# BtnCore.net
KiCad netlist of a schematic drawn in Altium Designer
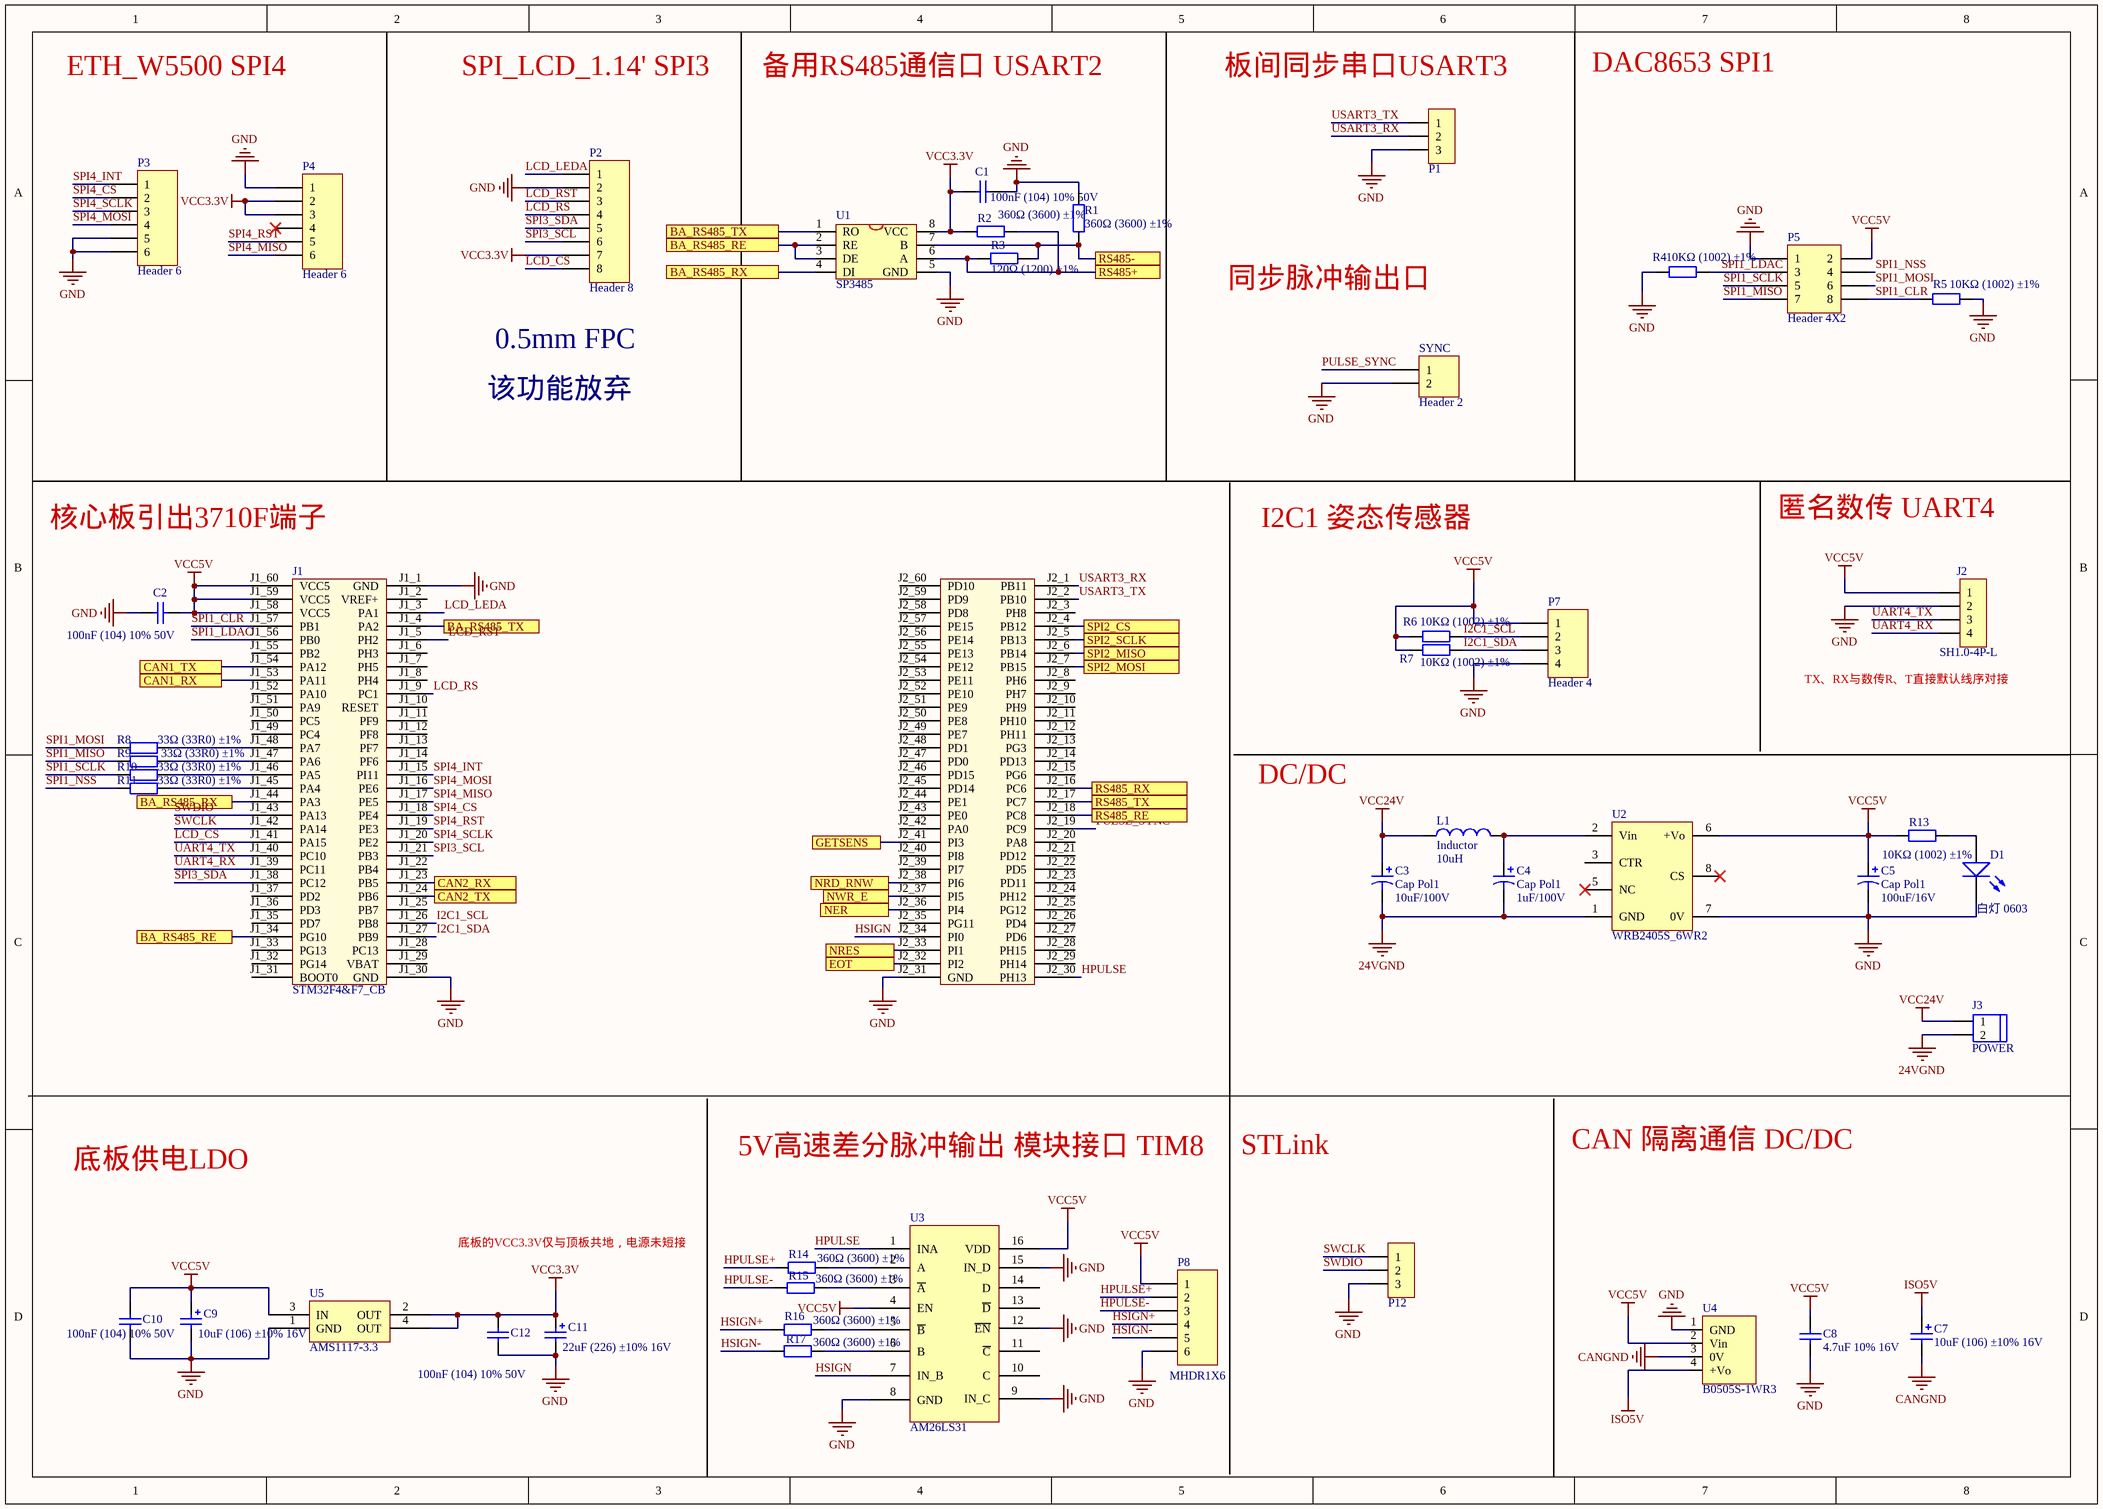
[diagram p0: BtnCore.SchDoc]

(export (version "E")
  (design (tool "Eeschema 10.0.6"))
  (components
    (comp (ref "C1")
      (value "100nF (104) 10% 50V")
      (footprint "0402_C")
      (description "贴片电容")
      (libsource (lib "Cap") (part "0603 100nF (104) 10% 50V"))
    )
    (comp (ref "C2")
      (value "100nF (104) 10% 50V")
      (footprint "0402_C")
      (description "贴片电容")
      (libsource (lib "Cap") (part "0603 100nF (104) 10% 50V"))
    )
    (comp (ref "C3")
      (value "Cap Pol1")
      (footprint "CAP-E8mm")
      (description "Polarized Capacitor (Radial)")
      (fields (field (name "ALTIUM_VALUE") "10uF/100V") (field (name "PUBLISHER") "Altium Limited"))
      (libsource (lib "Miscellaneous Devices") (part "Cap Pol1"))
    )
    (comp (ref "C4")
      (value "Cap Pol1")
      (footprint "CAP-E5mm")
      (description "Polarized Capacitor (Radial)")
      (fields (field (name "ALTIUM_VALUE") "1uF/100V") (field (name "PUBLISHER") "Altium Limited"))
      (libsource (lib "Miscellaneous Devices") (part "Cap Pol1"))
    )
    (comp (ref "C5")
      (value "Cap Pol1")
      (footprint "CAP-E8mm")
      (description "Polarized Capacitor (Radial)")
      (fields (field (name "ALTIUM_VALUE") "100uF/16V") (field (name "PUBLISHER") "Altium Limited"))
      (libsource (lib "Miscellaneous Devices") (part "Cap Pol1"))
    )
    (comp (ref "C7")
      (value "10uF (106) ±10% 16V")
      (footprint "CASE-A_3216")
      (description "钽电容")
      (libsource (lib "Miscellaneous Devices LC") (part "3216 10uF (106) 10% 16V"))
    )
    (comp (ref "C8")
      (value "4.7uF 10% 16V")
      (footprint "0603_C")
      (description "贴片电容")
      (libsource (lib "Cap") (part "0603 100nF (104) 10% 50V"))
    )
    (comp (ref "C9")
      (value "10uF (106) ±10% 16V")
      (footprint "CASE-A_3216")
      (description "钽电容")
      (libsource (lib "Cap") (part "3216 10uF (106) 10% 16V"))
    )
    (comp (ref "C10")
      (value "100nF (104) 10% 50V")
      (footprint "0402_C")
      (description "贴片电容")
      (libsource (lib "Cap") (part "0603 100nF (104) 10% 50V"))
    )
    (comp (ref "C11")
      (value "22uF (226) ±10% 16V")
      (footprint "CASE-B_3528")
      (description "钽电容")
      (libsource (lib "Cap") (part "3216 10uF (106) 10% 16V"))
    )
    (comp (ref "C12")
      (value "100nF (104) 10% 50V")
      (footprint "0402_C")
      (description "贴片电容")
      (libsource (lib "Cap") (part "0603 100nF (104) 10% 50V"))
    )
    (comp (ref "D1")
      (value "白灯 0603")
      (footprint "0603_LED_S1")
      (description "发光二极管")
      (libsource (lib "LED") (part "0603 白灯"))
    )
    (comp (ref "J1")
      (value "STM32F4&F7_CB")
      (footprint "STM32F4&F7_CB")
      (description "F429/746 Core Board")
      (libsource (lib "STM32F429_F746") (part "STM32F4&F7_CB"))
    )
    (comp (ref "J2")
      (value "SH1.0-4P-L")
      (footprint "SH1.0-4P-L")
      (description "4P接插件")
      (libsource (lib "4.14接插件-脚距1.0") (part "Header 4"))
    )
    (comp (ref "J3")
      (value "POWER")
      (footprint "HEAD2L-0.8")
      (libsource (lib "STM32F429_F746") (part "HEAD2"))
    )
    (comp (ref "L1")
      (value "Inductor")
      (footprint "0603_L")
      (fields (field (name "ALTIUM_VALUE") "10uH") (field (name "PUBLISHER") "Altium Limited"))
      (libsource (lib "Miscellaneous Devices") (part "Inductor"))
    )
    (comp (ref "P1")
      (value "SH1.0-3P")
      (footprint "SH1.0-3P-L")
      (description "3P接插件")
      (libsource (lib "4.14接插件-脚距1.0") (part "Header 3"))
    )
    (comp (ref "P2")
      (value "Header 8")
      (footprint "FPC0.5 2H-WS-8P")
      (description "Header, 8-Pin")
      (fields (field (name "PUBLISHER") "Altium Limited"))
      (libsource (lib "Miscellaneous Connectors") (part "Header 8"))
    )
    (comp (ref "P3")
      (value "Header 6")
      (footprint "HDR1X6")
      (description "Header, 6-Pin")
      (fields (field (name "PUBLISHER") "Altium Limited"))
      (libsource (lib "Miscellaneous Connectors") (part "Header 6"))
    )
    (comp (ref "P4")
      (value "Header 6")
      (footprint "HDR1X6")
      (description "Header, 6-Pin")
      (fields (field (name "PUBLISHER") "Altium Limited"))
      (libsource (lib "Miscellaneous Connectors") (part "Header 6"))
    )
    (comp (ref "P5")
      (value "Header 4X2")
      (footprint "HDR2X4")
      (description "Header, 4-Pin, Dual row")
      (fields (field (name "PUBLISHER") "Altium Limited"))
      (libsource (lib "Miscellaneous Connectors") (part "Header 4X2"))
    )
    (comp (ref "P7")
      (value "Header 4")
      (footprint "SH1.0-4P-L")
      (description "Header, 4-Pin")
      (fields (field (name "PUBLISHER") "Altium Limited"))
      (libsource (lib "Miscellaneous Connectors") (part "Header 4"))
    )
    (comp (ref "P8")
      (value "MHDR1X6")
      (footprint "SH1.0-6P-L")
      (description "Header, 6-Pin")
      (fields (field (name "PUBLISHER") "Altium Limited"))
      (libsource (lib "Miscellaneous Connectors") (part "MHDR1X6"))
    )
    (comp (ref "P12")
      (value "SH1.0-3P")
      (footprint "SH1.0-3P-L")
      (description "3P接插件")
      (libsource (lib "4.14接插件-脚距1.0") (part "Header 3"))
    )
    (comp (ref "R1")
      (value "360Ω (3600) ±1%")
      (footprint "0402_R")
      (description "贴片电阻")
      (libsource (lib "RES") (part "0603 360Ω (3600) 1%"))
    )
    (comp (ref "R2")
      (value "360Ω (3600) ±1%")
      (footprint "0402_R")
      (description "贴片电阻")
      (libsource (lib "") (part "0603 360Ω (3600) 1%_2"))
    )
    (comp (ref "R3")
      (value "120Ω (1200) ±1%")
      (footprint "0402_R")
      (description "贴片电阻")
      (libsource (lib "RES") (part "0603 120Ω (1200) 1%"))
    )
    (comp (ref "R4")
      (value "10KΩ (1002) ±1%")
      (footprint "0402_R")
      (description "贴片电阻")
      (libsource (lib "RES") (part "0805 100KΩ (1003) 1%"))
    )
    (comp (ref "R5")
      (value "10KΩ (1002) ±1%")
      (footprint "0402_R")
      (description "贴片电阻")
      (libsource (lib "RES") (part "0805 100KΩ (1003) 1%"))
    )
    (comp (ref "R6")
      (value "10KΩ (1002) ±1%")
      (footprint "0402_R")
      (description "贴片电阻")
      (libsource (lib "") (part "0805 100KΩ (1003) 1%_1"))
    )
    (comp (ref "R7")
      (value "10KΩ (1002) ±1%")
      (footprint "0402_R")
      (description "贴片电阻")
      (libsource (lib "") (part "0805 100KΩ (1003) 1%_1"))
    )
    (comp (ref "R8")
      (value "33Ω (33R0) ±1%")
      (footprint "0402_R")
      (description "贴片电阻")
      (libsource (lib "Miscellaneous Devices LC") (part "0603 33Ω (33R0) 1%"))
    )
    (comp (ref "R9")
      (value "33Ω (33R0) ±1%")
      (footprint "0402_R")
      (description "贴片电阻")
      (libsource (lib "Miscellaneous Devices LC") (part "0603 33Ω (33R0) 1%"))
    )
    (comp (ref "R10")
      (value "33Ω (33R0) ±1%")
      (footprint "0402_R")
      (description "贴片电阻")
      (libsource (lib "Miscellaneous Devices LC") (part "0603 33Ω (33R0) 1%"))
    )
    (comp (ref "R11")
      (value "33Ω (33R0) ±1%")
      (footprint "0402_R")
      (description "贴片电阻")
      (libsource (lib "Miscellaneous Devices LC") (part "0603 33Ω (33R0) 1%"))
    )
    (comp (ref "R13")
      (value "10KΩ (1002) ±1%")
      (footprint "0402_R")
      (description "贴片电阻")
      (libsource (lib "") (part "0805 100KΩ (1003) 1%_1"))
    )
    (comp (ref "R14")
      (value "360Ω (3600) ±1%")
      (footprint "0402_R")
      (description "贴片电阻")
      (libsource (lib "") (part "0603 360Ω (3600) 1%_1"))
    )
    (comp (ref "R15")
      (value "360Ω (3600) ±1%")
      (footprint "0402_R")
      (description "贴片电阻")
      (libsource (lib "") (part "0603 360Ω (3600) 1%_1"))
    )
    (comp (ref "R16")
      (value "360Ω (3600) ±1%")
      (footprint "0402_R")
      (description "贴片电阻")
      (libsource (lib "") (part "0603 360Ω (3600) 1%_1"))
    )
    (comp (ref "R17")
      (value "360Ω (3600) ±1%")
      (footprint "0402_R")
      (description "贴片电阻")
      (libsource (lib "") (part "0603 360Ω (3600) 1%_1"))
    )
    (comp (ref "SYNC")
      (value "Header 2")
      (footprint "HDR1X2")
      (description "Header, 2-Pin")
      (fields (field (name "PUBLISHER") "Altium Limited"))
      (libsource (lib "Miscellaneous Connectors") (part "Header 2"))
    )
    (comp (ref "U1") (value "SP3485") (footprint "SOP-8") (libsource (lib "STM32F429_F746") (part "MAX3485")))
    (comp (ref "U2")
      (value "WRB2405S_6WR2")
      (footprint "DCDC_SUCCEED-WRA_S/WRB-1/2/3W")
      (description "电源模块")
      (libsource (lib "Library") (part "DCDC-WRB"))
    )
    (comp (ref "U3")
      (value "AM26LS31")
      (footprint "SO-16_N")
      (description "AM32LS31 单端转差分芯片")
      (libsource (lib "CAS") (part "AM26LS31"))
    )
    (comp (ref "U4")
      (value "B0505S-1WR3")
      (footprint "B_S-1WR3")
      (libsource (lib "B_S-1WR3") (part "B_S-1WR3"))
    )
    (comp (ref "U5")
      (value "AMS1117-3.3")
      (footprint "SOT223_M")
      (description "3.3V稳压芯片")
      (libsource (lib "Library") (part "AMS1117"))
    )
  )
  (nets
    (net (code "1") (name "/BA_RS485_RE") (class "Default")
      (node (ref "J1") (pin "J1_34") (pinfunction "PG10_J1_34") (pintype "passive"))
      (node (ref "U1") (pin "2") (pinfunction "RE_2") (pintype "passive"))
      (node (ref "U1") (pin "3") (pinfunction "DE_3") (pintype "passive"))
    )
    (net (code "2") (name "/BA_RS485_RX") (class "Default")
      (node (ref "J1") (pin "J1_44") (pinfunction "PA3_J1_44") (pintype "passive"))
      (node (ref "U1") (pin "4") (pinfunction "DI_4") (pintype "passive"))
    )
    (net (code "3") (name "/BA_RS485_TX") (class "Default")
      (node (ref "J1") (pin "J1_4") (pinfunction "PA2_J1_4") (pintype "passive"))
      (node (ref "U1") (pin "1") (pinfunction "RO_1") (pintype "passive"))
    )
    (net (code "4") (name "/CAN1_RX") (class "Default")
      (node (ref "J1") (pin "J1_53") (pinfunction "PA11_J1_53") (pintype "passive"))
    )
    (net (code "5") (name "/CAN1_TX") (class "Default")
      (node (ref "J1") (pin "J1_54") (pinfunction "PA12_J1_54") (pintype "passive"))
    )
    (net (code "6") (name "/CAN2_RX") (class "Default")
      (node (ref "J1") (pin "J1_23") (pinfunction "PB5_J1_23") (pintype "passive"))
    )
    (net (code "7") (name "/CAN2_TX") (class "Default")
      (node (ref "J1") (pin "J1_24") (pinfunction "PB6_J1_24") (pintype "passive"))
    )
    (net (code "8") (name "/EOT") (class "Default")
      (node (ref "J1") (pin "J2_32") (pinfunction "PI2_J2_32") (pintype "passive"))
    )
    (net (code "9") (name "/GETSENS") (class "Default")
      (node (ref "J1") (pin "J2_41") (pinfunction "PI3_J2_41") (pintype "passive"))
    )
    (net (code "10") (name "/HPULSE") (class "Default")
      (node (ref "J1") (pin "J2_30") (pinfunction "PH13_J2_30") (pintype "passive"))
      (node (ref "U3") (pin "1") (pinfunction "INA_1") (pintype "passive"))
    )
    (net (code "11") (name "/HPULSE+") (class "Default")
      (node (ref "P8") (pin "2") (pinfunction "2_2") (pintype "passive"))
      (node (ref "R14") (pin "2") (pinfunction "2_2") (pintype "passive"))
    )
    (net (code "12") (name "/HPULSE-") (class "Default")
      (node (ref "P8") (pin "3") (pinfunction "3_3") (pintype "passive"))
      (node (ref "R15") (pin "2") (pinfunction "2_2") (pintype "passive"))
    )
    (net (code "13") (name "/HSIGN") (class "Default")
      (node (ref "J1") (pin "J2_34") (pinfunction "PI0_J2_34") (pintype "passive"))
      (node (ref "U3") (pin "7") (pinfunction "IN_B_7") (pintype "passive"))
    )
    (net (code "14") (name "/HSIGN+") (class "Default")
      (node (ref "P8") (pin "4") (pinfunction "4_4") (pintype "passive"))
      (node (ref "R16") (pin "2") (pinfunction "2_2") (pintype "passive"))
    )
    (net (code "15") (name "/HSIGN-") (class "Default")
      (node (ref "P8") (pin "5") (pinfunction "5_5") (pintype "passive"))
      (node (ref "R17") (pin "2") (pinfunction "2_2") (pintype "passive"))
    )
    (net (code "16") (name "/I2C1_SCL") (class "Default")
      (node (ref "J1") (pin "J1_26") (pinfunction "PB8_J1_26") (pintype "passive"))
      (node (ref "P7") (pin "2") (pinfunction "2_2") (pintype "passive"))
      (node (ref "R6") (pin "2") (pinfunction "2_2") (pintype "passive"))
    )
    (net (code "17") (name "/I2C1_SDA") (class "Default")
      (node (ref "J1") (pin "J1_27") (pinfunction "PB9_J1_27") (pintype "passive"))
      (node (ref "P7") (pin "3") (pinfunction "3_3") (pintype "passive"))
      (node (ref "R7") (pin "2") (pinfunction "2_2") (pintype "passive"))
    )
    (net (code "18") (name "/LCD_CS") (class "Default")
      (node (ref "J1") (pin "J1_41") (pinfunction "PA15_J1_41") (pintype "passive"))
      (node (ref "P2") (pin "8") (pinfunction "8_8") (pintype "passive"))
    )
    (net (code "19") (name "/LCD_LEDA") (class "Default")
      (node (ref "J1") (pin "J1_3") (pinfunction "PA1_J1_3") (pintype "passive"))
      (node (ref "P2") (pin "1") (pinfunction "1_1") (pintype "passive"))
    )
    (net (code "20") (name "/LCD_RS") (class "Default")
      (node (ref "J1") (pin "J1_9") (pinfunction "PC1_J1_9") (pintype "passive"))
      (node (ref "P2") (pin "4") (pinfunction "4_4") (pintype "passive"))
    )
    (net (code "21") (name "/LCD_RST") (class "Default")
      (node (ref "J1") (pin "J1_5") (pinfunction "PH2_J1_5") (pintype "passive"))
      (node (ref "P2") (pin "3") (pinfunction "3_3") (pintype "passive"))
    )
    (net (code "22") (name "/NER") (class "Default")
      (node (ref "J1") (pin "J2_36") (pinfunction "PI4_J2_36") (pintype "passive"))
    )
    (net (code "23") (name "/NRD_RNW") (class "Default")
      (node (ref "J1") (pin "J2_38") (pinfunction "PI6_J2_38") (pintype "passive"))
    )
    (net (code "24") (name "/NRES") (class "Default")
      (node (ref "J1") (pin "J2_33") (pinfunction "PI1_J2_33") (pintype "passive"))
    )
    (net (code "25") (name "/NWR_E") (class "Default")
      (node (ref "J1") (pin "J2_37") (pinfunction "PI5_J2_37") (pintype "passive"))
    )
    (net (code "26") (name "/PULSE_SYNC") (class "Default")
      (node (ref "J1") (pin "J2_19") (pinfunction "PC9_J2_19") (pintype "passive"))
      (node (ref "SYNC") (pin "1") (pinfunction "1_1") (pintype "passive"))
    )
    (net (code "27") (name "/RS485+") (class "Default")
      (node (ref "R2") (pin "2") (pinfunction "2_2") (pintype "passive"))
      (node (ref "R3") (pin "2") (pinfunction "2_2") (pintype "passive"))
      (node (ref "U1") (pin "6") (pinfunction "A_6") (pintype "passive"))
    )
    (net (code "28") (name "/RS485-") (class "Default")
      (node (ref "R1") (pin "1") (pinfunction "1_1") (pintype "passive"))
      (node (ref "R3") (pin "1") (pinfunction "1_1") (pintype "passive"))
      (node (ref "U1") (pin "7") (pinfunction "B_7") (pintype "passive"))
    )
    (net (code "29") (name "/RS485_RE") (class "Default")
      (node (ref "J1") (pin "J2_18") (pinfunction "PC8_J2_18") (pintype "passive"))
    )
    (net (code "30") (name "/RS485_RX") (class "Default")
      (node (ref "J1") (pin "J2_16") (pinfunction "PC6_J2_16") (pintype "passive"))
    )
    (net (code "31") (name "/RS485_TX") (class "Default")
      (node (ref "J1") (pin "J2_17") (pinfunction "PC7_J2_17") (pintype "passive"))
    )
    (net (code "32") (name "/SPI1_CLR") (class "Default")
      (node (ref "J1") (pin "J1_57") (pinfunction "PB1_J1_57") (pintype "passive"))
      (node (ref "P5") (pin "8") (pinfunction "8_8") (pintype "passive"))
      (node (ref "R5") (pin "2") (pinfunction "2_2") (pintype "passive"))
    )
    (net (code "33") (name "/SPI1_LDAC") (class "Default")
      (node (ref "J1") (pin "J1_56") (pinfunction "PB0_J1_56") (pintype "passive"))
      (node (ref "P5") (pin "3") (pinfunction "3_3") (pintype "passive"))
      (node (ref "R4") (pin "1") (pinfunction "1_1") (pintype "passive"))
    )
    (net (code "34") (name "/SPI1_MISO") (class "Default")
      (node (ref "P5") (pin "7") (pinfunction "7_7") (pintype "passive"))
      (node (ref "R9") (pin "1") (pinfunction "1_1") (pintype "passive"))
    )
    (net (code "35") (name "/SPI1_MOSI") (class "Default")
      (node (ref "P5") (pin "6") (pinfunction "6_6") (pintype "passive"))
      (node (ref "R8") (pin "1") (pinfunction "1_1") (pintype "passive"))
    )
    (net (code "36") (name "/SPI1_NSS") (class "Default")
      (node (ref "P5") (pin "4") (pinfunction "4_4") (pintype "passive"))
      (node (ref "R11") (pin "1") (pinfunction "1_1") (pintype "passive"))
    )
    (net (code "37") (name "/SPI1_SCLK") (class "Default")
      (node (ref "P5") (pin "5") (pinfunction "5_5") (pintype "passive"))
      (node (ref "R10") (pin "1") (pinfunction "1_1") (pintype "passive"))
    )
    (net (code "38") (name "/SPI2_CS") (class "Default")
      (node (ref "J1") (pin "J2_4") (pinfunction "PB12_J2_4") (pintype "passive"))
    )
    (net (code "39") (name "/SPI2_MISO") (class "Default")
      (node (ref "J1") (pin "J2_6") (pinfunction "PB14_J2_6") (pintype "passive"))
    )
    (net (code "40") (name "/SPI2_MOSI") (class "Default")
      (node (ref "J1") (pin "J2_7") (pinfunction "PB15_J2_7") (pintype "passive"))
    )
    (net (code "41") (name "/SPI2_SCLK") (class "Default")
      (node (ref "J1") (pin "J2_5") (pinfunction "PB13_J2_5") (pintype "passive"))
    )
    (net (code "42") (name "/SPI3_SCL") (class "Default")
      (node (ref "J1") (pin "J1_21") (pinfunction "PB3_J1_21") (pintype "passive"))
      (node (ref "P2") (pin "6") (pinfunction "6_6") (pintype "passive"))
    )
    (net (code "43") (name "/SPI3_SDA") (class "Default")
      (node (ref "J1") (pin "J1_38") (pinfunction "PC12_J1_38") (pintype "passive"))
      (node (ref "P2") (pin "5") (pinfunction "5_5") (pintype "passive"))
    )
    (net (code "44") (name "/SPI4_CS") (class "Default")
      (node (ref "J1") (pin "J1_18") (pinfunction "PE4_J1_18") (pintype "passive"))
      (node (ref "P3") (pin "2") (pinfunction "2_2") (pintype "passive"))
    )
    (net (code "45") (name "/SPI4_INT") (class "Default")
      (node (ref "J1") (pin "J1_15") (pinfunction "PI11_J1_15") (pintype "passive"))
      (node (ref "P3") (pin "1") (pinfunction "1_1") (pintype "passive"))
    )
    (net (code "46") (name "/SPI4_MISO") (class "Default")
      (node (ref "J1") (pin "J1_17") (pinfunction "PE5_J1_17") (pintype "passive"))
      (node (ref "P4") (pin "6") (pinfunction "6_6") (pintype "passive"))
    )
    (net (code "47") (name "/SPI4_MOSI") (class "Default")
      (node (ref "J1") (pin "J1_16") (pinfunction "PE6_J1_16") (pintype "passive"))
      (node (ref "P3") (pin "4") (pinfunction "4_4") (pintype "passive"))
    )
    (net (code "48") (name "/SPI4_RST") (class "Default")
      (node (ref "J1") (pin "J1_19") (pinfunction "PE3_J1_19") (pintype "passive"))
      (node (ref "P4") (pin "5") (pinfunction "5_5") (pintype "passive"))
    )
    (net (code "49") (name "/SPI4_SCLK") (class "Default")
      (node (ref "J1") (pin "J1_20") (pinfunction "PE2_J1_20") (pintype "passive"))
      (node (ref "P3") (pin "3") (pinfunction "3_3") (pintype "passive"))
    )
    (net (code "50") (name "/SWCLK") (class "Default")
      (node (ref "J1") (pin "J1_42") (pinfunction "PA14_J1_42") (pintype "passive"))
      (node (ref "P12") (pin "1") (pinfunction "1_1") (pintype "passive"))
    )
    (net (code "51") (name "/SWDIO") (class "Default")
      (node (ref "J1") (pin "J1_43") (pinfunction "PA13_J1_43") (pintype "passive"))
      (node (ref "P12") (pin "2") (pinfunction "2_2") (pintype "passive"))
    )
    (net (code "52") (name "/UART4_RX") (class "Default")
      (node (ref "J1") (pin "J1_39") (pinfunction "PC11_J1_39") (pintype "passive"))
      (node (ref "J2") (pin "4") (pinfunction "4_4") (pintype "passive"))
    )
    (net (code "53") (name "/UART4_TX") (class "Default")
      (node (ref "J1") (pin "J1_40") (pinfunction "PC10_J1_40") (pintype "passive"))
      (node (ref "J2") (pin "3") (pinfunction "3_3") (pintype "passive"))
    )
    (net (code "54") (name "/USART3_RX") (class "Default")
      (node (ref "J1") (pin "J2_1") (pinfunction "PB11_J2_1") (pintype "passive"))
      (node (ref "P1") (pin "2") (pinfunction "2_2") (pintype "passive"))
    )
    (net (code "55") (name "/USART3_TX") (class "Default")
      (node (ref "J1") (pin "J2_2") (pinfunction "PB10_J2_2") (pintype "passive"))
      (node (ref "P1") (pin "1") (pinfunction "1_1") (pintype "passive"))
    )
    (net (code "56") (name "24VGND") (class "Default")
      (node (ref "C3") (pin "2") (pinfunction "2_2") (pintype "passive"))
      (node (ref "C4") (pin "2") (pinfunction "2_2") (pintype "passive"))
      (node (ref "J3") (pin "2") (pinfunction "2_2") (pintype "passive"))
      (node (ref "U2") (pin "1") (pinfunction "GND_1") (pintype "passive"))
    )
    (net (code "57") (name "CANGND") (class "Default")
      (node (ref "C7") (pin "2") (pinfunction "2_2") (pintype "passive"))
      (node (ref "U4") (pin "3") (pinfunction "0V_3") (pintype "passive"))
    )
    (net (code "58") (name "GND") (class "Default")
      (node (ref "C1") (pin "1") (pinfunction "1_1") (pintype "passive"))
      (node (ref "C10") (pin "2") (pinfunction "2_2") (pintype "passive"))
      (node (ref "C11") (pin "2") (pinfunction "2_2") (pintype "passive"))
      (node (ref "C12") (pin "2") (pinfunction "2_2") (pintype "passive"))
      (node (ref "C2") (pin "1") (pinfunction "1_1") (pintype "passive"))
      (node (ref "C5") (pin "2") (pinfunction "2_2") (pintype "passive"))
      (node (ref "C8") (pin "2") (pinfunction "2_2") (pintype "passive"))
      (node (ref "C9") (pin "2") (pinfunction "2_2") (pintype "passive"))
      (node (ref "D1") (pin "K") (pinfunction "K_K") (pintype "passive"))
      (node (ref "J1") (pin "J1_1") (pinfunction "GND_J1_1") (pintype "passive"))
      (node (ref "J1") (pin "J1_30") (pinfunction "GND_J1_30") (pintype "passive"))
      (node (ref "J1") (pin "J2_31") (pinfunction "GND_J2_31") (pintype "passive"))
      (node (ref "J2") (pin "2") (pinfunction "2_2") (pintype "passive"))
      (node (ref "P1") (pin "3") (pinfunction "3_3") (pintype "passive"))
      (node (ref "P12") (pin "3") (pinfunction "3_3") (pintype "passive"))
      (node (ref "P2") (pin "2") (pinfunction "2_2") (pintype "passive"))
      (node (ref "P3") (pin "5") (pinfunction "5_5") (pintype "passive"))
      (node (ref "P3") (pin "6") (pinfunction "6_6") (pintype "passive"))
      (node (ref "P4") (pin "1") (pinfunction "1_1") (pintype "passive"))
      (node (ref "P5") (pin "1") (pinfunction "1_1") (pintype "passive"))
      (node (ref "P7") (pin "4") (pinfunction "4_4") (pintype "passive"))
      (node (ref "P8") (pin "6") (pinfunction "6_6") (pintype "passive"))
      (node (ref "R1") (pin "2") (pinfunction "2_2") (pintype "passive"))
      (node (ref "R4") (pin "2") (pinfunction "2_2") (pintype "passive"))
      (node (ref "R5") (pin "1") (pinfunction "1_1") (pintype "passive"))
      (node (ref "SYNC") (pin "2") (pinfunction "2_2") (pintype "passive"))
      (node (ref "U1") (pin "5") (pinfunction "GND_5") (pintype "passive"))
      (node (ref "U2") (pin "7") (pinfunction "0V_7") (pintype "passive"))
      (node (ref "U3") (pin "12") (pinfunction "~{EN}_12") (pintype "passive"))
      (node (ref "U3") (pin "15") (pinfunction "IN_D_15") (pintype "passive"))
      (node (ref "U3") (pin "8") (pinfunction "GND_8") (pintype "passive"))
      (node (ref "U3") (pin "9") (pinfunction "IN_C_9") (pintype "passive"))
      (node (ref "U4") (pin "1") (pinfunction "GND_1") (pintype "passive"))
      (node (ref "U5") (pin "1") (pinfunction "GND_1") (pintype "passive"))
    )
    (net (code "59") (name "ISO5V") (class "Default")
      (node (ref "C7") (pin "1") (pinfunction "1_1") (pintype "passive"))
      (node (ref "U4") (pin "4") (pinfunction "+Vo_4") (pintype "passive"))
    )
    (net (code "60") (name "Net-(D1-PadA)") (class "Default")
      (node (ref "D1") (pin "A") (pinfunction "A_A") (pintype "passive"))
      (node (ref "R13") (pin "2") (pinfunction "2_2") (pintype "passive"))
    )
    (net (code "61") (name "Net-(J1-PA4)") (class "Default")
      (node (ref "J1") (pin "J1_45") (pinfunction "PA4_J1_45") (pintype "passive"))
      (node (ref "R11") (pin "2") (pinfunction "2_2") (pintype "passive"))
    )
    (net (code "62") (name "Net-(J1-PA5)") (class "Default")
      (node (ref "J1") (pin "J1_46") (pinfunction "PA5_J1_46") (pintype "passive"))
      (node (ref "R10") (pin "2") (pinfunction "2_2") (pintype "passive"))
    )
    (net (code "63") (name "Net-(J1-PA6)") (class "Default")
      (node (ref "J1") (pin "J1_47") (pinfunction "PA6_J1_47") (pintype "passive"))
      (node (ref "R9") (pin "2") (pinfunction "2_2") (pintype "passive"))
    )
    (net (code "64") (name "Net-(J1-PA7)") (class "Default")
      (node (ref "J1") (pin "J1_48") (pinfunction "PA7_J1_48") (pintype "passive"))
      (node (ref "R8") (pin "2") (pinfunction "2_2") (pintype "passive"))
    )
    (net (code "65") (name "Net-(U2-Vin)") (class "Default")
      (node (ref "C4") (pin "1") (pinfunction "1_1") (pintype "passive"))
      (node (ref "L1") (pin "2") (pinfunction "2_2") (pintype "passive"))
      (node (ref "U2") (pin "2") (pinfunction "Vin_2") (pintype "passive"))
    )
    (net (code "66") (name "Net-(U3-A)") (class "Default")
      (node (ref "R14") (pin "1") (pinfunction "1_1") (pintype "passive"))
      (node (ref "U3") (pin "2") (pinfunction "A_2") (pintype "passive"))
    )
    (net (code "67") (name "Net-(U3-B)") (class "Default")
      (node (ref "R17") (pin "1") (pinfunction "1_1") (pintype "passive"))
      (node (ref "U3") (pin "6") (pinfunction "B_6") (pintype "passive"))
    )
    (net (code "68") (name "Net-(U3-~{A})") (class "Default")
      (node (ref "R15") (pin "1") (pinfunction "1_1") (pintype "passive"))
      (node (ref "U3") (pin "3") (pinfunction "~{A}_3") (pintype "passive"))
    )
    (net (code "69") (name "Net-(U3-~{B})") (class "Default")
      (node (ref "R16") (pin "1") (pinfunction "1_1") (pintype "passive"))
      (node (ref "U3") (pin "5") (pinfunction "~{B}_5") (pintype "passive"))
    )
    (net (code "70") (name "VCC3.3V") (class "Default")
      (node (ref "C1") (pin "2") (pinfunction "2_2") (pintype "passive"))
      (node (ref "C11") (pin "1") (pinfunction "1_1") (pintype "passive"))
      (node (ref "C12") (pin "1") (pinfunction "1_1") (pintype "passive"))
      (node (ref "P2") (pin "7") (pinfunction "7_7") (pintype "passive"))
      (node (ref "P4") (pin "2") (pinfunction "2_2") (pintype "passive"))
      (node (ref "P4") (pin "3") (pinfunction "3_3") (pintype "passive"))
      (node (ref "R2") (pin "1") (pinfunction "1_1") (pintype "passive"))
      (node (ref "U1") (pin "8") (pinfunction "VCC_8") (pintype "passive"))
      (node (ref "U5") (pin "2") (pinfunction "OUT_2") (pintype "passive"))
      (node (ref "U5") (pin "4") (pinfunction "OUT_4") (pintype "passive"))
    )
    (net (code "71") (name "VCC5V") (class "Default")
      (node (ref "C10") (pin "1") (pinfunction "1_1") (pintype "passive"))
      (node (ref "C2") (pin "2") (pinfunction "2_2") (pintype "passive"))
      (node (ref "C5") (pin "1") (pinfunction "1_1") (pintype "passive"))
      (node (ref "C8") (pin "1") (pinfunction "1_1") (pintype "passive"))
      (node (ref "C9") (pin "1") (pinfunction "1_1") (pintype "passive"))
      (node (ref "J1") (pin "J1_58") (pinfunction "VCC5_J1_58") (pintype "passive"))
      (node (ref "J1") (pin "J1_59") (pinfunction "VCC5_J1_59") (pintype "passive"))
      (node (ref "J1") (pin "J1_60") (pinfunction "VCC5_J1_60") (pintype "passive"))
      (node (ref "J2") (pin "1") (pinfunction "1_1") (pintype "passive"))
      (node (ref "P5") (pin "2") (pinfunction "2_2") (pintype "passive"))
      (node (ref "P7") (pin "1") (pinfunction "1_1") (pintype "passive"))
      (node (ref "P8") (pin "1") (pinfunction "1_1") (pintype "passive"))
      (node (ref "R13") (pin "1") (pinfunction "1_1") (pintype "passive"))
      (node (ref "R6") (pin "1") (pinfunction "1_1") (pintype "passive"))
      (node (ref "R7") (pin "1") (pinfunction "1_1") (pintype "passive"))
      (node (ref "U2") (pin "6") (pinfunction "+Vo_6") (pintype "passive"))
      (node (ref "U3") (pin "16") (pinfunction "VDD_16") (pintype "passive"))
      (node (ref "U3") (pin "4") (pinfunction "EN_4") (pintype "passive"))
      (node (ref "U4") (pin "2") (pinfunction "Vin_2") (pintype "passive"))
      (node (ref "U5") (pin "3") (pinfunction "IN_3") (pintype "passive"))
    )
    (net (code "72") (name "VCC24V") (class "Default")
      (node (ref "C3") (pin "1") (pinfunction "1_1") (pintype "passive"))
      (node (ref "J3") (pin "1") (pinfunction "1_1") (pintype "passive"))
      (node (ref "L1") (pin "1") (pinfunction "1_1") (pintype "passive"))
    )
    (net (code "73") (name "unconnected-(J1-BOOT0-PadJ1_31)") (class "Default")
      (node (ref "J1") (pin "J1_31") (pinfunction "BOOT0_J1_31") (pintype "passive"))
    )
    (net (code "74") (name "unconnected-(J1-PA0-PadJ2_42)") (class "Default")
      (node (ref "J1") (pin "J2_42") (pinfunction "PA0_J2_42") (pintype "passive"))
    )
    (net (code "75") (name "unconnected-(J1-PA8-PadJ2_20)") (class "Default")
      (node (ref "J1") (pin "J2_20") (pinfunction "PA8_J2_20") (pintype "passive"))
    )
    (net (code "76") (name "unconnected-(J1-PA9-PadJ1_51)") (class "Default")
      (node (ref "J1") (pin "J1_51") (pinfunction "PA9_J1_51") (pintype "passive"))
    )
    (net (code "77") (name "unconnected-(J1-PA10-PadJ1_52)") (class "Default")
      (node (ref "J1") (pin "J1_52") (pinfunction "PA10_J1_52") (pintype "passive"))
    )
    (net (code "78") (name "unconnected-(J1-PB2-PadJ1_55)") (class "Default")
      (node (ref "J1") (pin "J1_55") (pinfunction "PB2_J1_55") (pintype "passive"))
    )
    (net (code "79") (name "unconnected-(J1-PB4-PadJ1_22)") (class "Default")
      (node (ref "J1") (pin "J1_22") (pinfunction "PB4_J1_22") (pintype "passive"))
    )
    (net (code "80") (name "unconnected-(J1-PB7-PadJ1_25)") (class "Default")
      (node (ref "J1") (pin "J1_25") (pinfunction "PB7_J1_25") (pintype "passive"))
    )
    (net (code "81") (name "unconnected-(J1-PC4-PadJ1_49)") (class "Default")
      (node (ref "J1") (pin "J1_49") (pinfunction "PC4_J1_49") (pintype "passive"))
    )
    (net (code "82") (name "unconnected-(J1-PC5-PadJ1_50)") (class "Default")
      (node (ref "J1") (pin "J1_50") (pinfunction "PC5_J1_50") (pintype "passive"))
    )
    (net (code "83") (name "unconnected-(J1-PC13-PadJ1_28)") (class "Default")
      (node (ref "J1") (pin "J1_28") (pinfunction "PC13_J1_28") (pintype "passive"))
    )
    (net (code "84") (name "unconnected-(J1-PD0-PadJ2_47)") (class "Default")
      (node (ref "J1") (pin "J2_47") (pinfunction "PD0_J2_47") (pintype "passive"))
    )
    (net (code "85") (name "unconnected-(J1-PD1-PadJ2_48)") (class "Default")
      (node (ref "J1") (pin "J2_48") (pinfunction "PD1_J2_48") (pintype "passive"))
    )
    (net (code "86") (name "unconnected-(J1-PD2-PadJ1_37)") (class "Default")
      (node (ref "J1") (pin "J1_37") (pinfunction "PD2_J1_37") (pintype "passive"))
    )
    (net (code "87") (name "unconnected-(J1-PD3-PadJ1_36)") (class "Default")
      (node (ref "J1") (pin "J1_36") (pinfunction "PD3_J1_36") (pintype "passive"))
    )
    (net (code "88") (name "unconnected-(J1-PD4-PadJ2_26)") (class "Default")
      (node (ref "J1") (pin "J2_26") (pinfunction "PD4_J2_26") (pintype "passive"))
    )
    (net (code "89") (name "unconnected-(J1-PD5-PadJ2_22)") (class "Default")
      (node (ref "J1") (pin "J2_22") (pinfunction "PD5_J2_22") (pintype "passive"))
    )
    (net (code "90") (name "unconnected-(J1-PD6-PadJ2_27)") (class "Default")
      (node (ref "J1") (pin "J2_27") (pinfunction "PD6_J2_27") (pintype "passive"))
    )
    (net (code "91") (name "unconnected-(J1-PD7-PadJ1_35)") (class "Default")
      (node (ref "J1") (pin "J1_35") (pinfunction "PD7_J1_35") (pintype "passive"))
    )
    (net (code "92") (name "unconnected-(J1-PD8-PadJ2_58)") (class "Default")
      (node (ref "J1") (pin "J2_58") (pinfunction "PD8_J2_58") (pintype "passive"))
    )
    (net (code "93") (name "unconnected-(J1-PD9-PadJ2_59)") (class "Default")
      (node (ref "J1") (pin "J2_59") (pinfunction "PD9_J2_59") (pintype "passive"))
    )
    (net (code "94") (name "unconnected-(J1-PD10-PadJ2_60)") (class "Default")
      (node (ref "J1") (pin "J2_60") (pinfunction "PD10_J2_60") (pintype "passive"))
    )
    (net (code "95") (name "unconnected-(J1-PD11-PadJ2_23)") (class "Default")
      (node (ref "J1") (pin "J2_23") (pinfunction "PD11_J2_23") (pintype "passive"))
    )
    (net (code "96") (name "unconnected-(J1-PD12-PadJ2_21)") (class "Default")
      (node (ref "J1") (pin "J2_21") (pinfunction "PD12_J2_21") (pintype "passive"))
    )
    (net (code "97") (name "unconnected-(J1-PD13-PadJ2_14)") (class "Default")
      (node (ref "J1") (pin "J2_14") (pinfunction "PD13_J2_14") (pintype "passive"))
    )
    (net (code "98") (name "unconnected-(J1-PD14-PadJ2_45)") (class "Default")
      (node (ref "J1") (pin "J2_45") (pinfunction "PD14_J2_45") (pintype "passive"))
    )
    (net (code "99") (name "unconnected-(J1-PD15-PadJ2_46)") (class "Default")
      (node (ref "J1") (pin "J2_46") (pinfunction "PD15_J2_46") (pintype "passive"))
    )
    (net (code "100") (name "unconnected-(J1-PE0-PadJ2_43)") (class "Default")
      (node (ref "J1") (pin "J2_43") (pinfunction "PE0_J2_43") (pintype "passive"))
    )
    (net (code "101") (name "unconnected-(J1-PE1-PadJ2_44)") (class "Default")
      (node (ref "J1") (pin "J2_44") (pinfunction "PE1_J2_44") (pintype "passive"))
    )
    (net (code "102") (name "unconnected-(J1-PE7-PadJ2_49)") (class "Default")
      (node (ref "J1") (pin "J2_49") (pinfunction "PE7_J2_49") (pintype "passive"))
    )
    (net (code "103") (name "unconnected-(J1-PE8-PadJ2_50)") (class "Default")
      (node (ref "J1") (pin "J2_50") (pinfunction "PE8_J2_50") (pintype "passive"))
    )
    (net (code "104") (name "unconnected-(J1-PE9-PadJ2_51)") (class "Default")
      (node (ref "J1") (pin "J2_51") (pinfunction "PE9_J2_51") (pintype "passive"))
    )
    (net (code "105") (name "unconnected-(J1-PE10-PadJ2_52)") (class "Default")
      (node (ref "J1") (pin "J2_52") (pinfunction "PE10_J2_52") (pintype "passive"))
    )
    (net (code "106") (name "unconnected-(J1-PE11-PadJ2_53)") (class "Default")
      (node (ref "J1") (pin "J2_53") (pinfunction "PE11_J2_53") (pintype "passive"))
    )
    (net (code "107") (name "unconnected-(J1-PE12-PadJ2_54)") (class "Default")
      (node (ref "J1") (pin "J2_54") (pinfunction "PE12_J2_54") (pintype "passive"))
    )
    (net (code "108") (name "unconnected-(J1-PE13-PadJ2_55)") (class "Default")
      (node (ref "J1") (pin "J2_55") (pinfunction "PE13_J2_55") (pintype "passive"))
    )
    (net (code "109") (name "unconnected-(J1-PE14-PadJ2_56)") (class "Default")
      (node (ref "J1") (pin "J2_56") (pinfunction "PE14_J2_56") (pintype "passive"))
    )
    (net (code "110") (name "unconnected-(J1-PE15-PadJ2_57)") (class "Default")
      (node (ref "J1") (pin "J2_57") (pinfunction "PE15_J2_57") (pintype "passive"))
    )
    (net (code "111") (name "unconnected-(J1-PF6-PadJ1_14)") (class "Default")
      (node (ref "J1") (pin "J1_14") (pinfunction "PF6_J1_14") (pintype "passive"))
    )
    (net (code "112") (name "unconnected-(J1-PF7-PadJ1_13)") (class "Default")
      (node (ref "J1") (pin "J1_13") (pinfunction "PF7_J1_13") (pintype "passive"))
    )
    (net (code "113") (name "unconnected-(J1-PF8-PadJ1_12)") (class "Default")
      (node (ref "J1") (pin "J1_12") (pinfunction "PF8_J1_12") (pintype "passive"))
    )
    (net (code "114") (name "unconnected-(J1-PF9-PadJ1_11)") (class "Default")
      (node (ref "J1") (pin "J1_11") (pinfunction "PF9_J1_11") (pintype "passive"))
    )
    (net (code "115") (name "unconnected-(J1-PG3-PadJ2_13)") (class "Default")
      (node (ref "J1") (pin "J2_13") (pinfunction "PG3_J2_13") (pintype "passive"))
    )
    (net (code "116") (name "unconnected-(J1-PG6-PadJ2_15)") (class "Default")
      (node (ref "J1") (pin "J2_15") (pinfunction "PG6_J2_15") (pintype "passive"))
    )
    (net (code "117") (name "unconnected-(J1-PG11-PadJ2_35)") (class "Default")
      (node (ref "J1") (pin "J2_35") (pinfunction "PG11_J2_35") (pintype "passive"))
    )
    (net (code "118") (name "unconnected-(J1-PG12-PadJ2_25)") (class "Default")
      (node (ref "J1") (pin "J2_25") (pinfunction "PG12_J2_25") (pintype "passive"))
    )
    (net (code "119") (name "unconnected-(J1-PG13-PadJ1_33)") (class "Default")
      (node (ref "J1") (pin "J1_33") (pinfunction "PG13_J1_33") (pintype "passive"))
    )
    (net (code "120") (name "unconnected-(J1-PG14-PadJ1_32)") (class "Default")
      (node (ref "J1") (pin "J1_32") (pinfunction "PG14_J1_32") (pintype "passive"))
    )
    (net (code "121") (name "unconnected-(J1-PH3-PadJ1_6)") (class "Default")
      (node (ref "J1") (pin "J1_6") (pinfunction "PH3_J1_6") (pintype "passive"))
    )
    (net (code "122") (name "unconnected-(J1-PH4-PadJ1_8)") (class "Default")
      (node (ref "J1") (pin "J1_8") (pinfunction "PH4_J1_8") (pintype "passive"))
    )
    (net (code "123") (name "unconnected-(J1-PH5-PadJ1_7)") (class "Default")
      (node (ref "J1") (pin "J1_7") (pinfunction "PH5_J1_7") (pintype "passive"))
    )
    (net (code "124") (name "unconnected-(J1-PH6-PadJ2_8)") (class "Default")
      (node (ref "J1") (pin "J2_8") (pinfunction "PH6_J2_8") (pintype "passive"))
    )
    (net (code "125") (name "unconnected-(J1-PH7-PadJ2_9)") (class "Default")
      (node (ref "J1") (pin "J2_9") (pinfunction "PH7_J2_9") (pintype "passive"))
    )
    (net (code "126") (name "unconnected-(J1-PH8-PadJ2_3)") (class "Default")
      (node (ref "J1") (pin "J2_3") (pinfunction "PH8_J2_3") (pintype "passive"))
    )
    (net (code "127") (name "unconnected-(J1-PH9-PadJ2_10)") (class "Default")
      (node (ref "J1") (pin "J2_10") (pinfunction "PH9_J2_10") (pintype "passive"))
    )
    (net (code "128") (name "unconnected-(J1-PH10-PadJ2_11)") (class "Default")
      (node (ref "J1") (pin "J2_11") (pinfunction "PH10_J2_11") (pintype "passive"))
    )
    (net (code "129") (name "unconnected-(J1-PH11-PadJ2_12)") (class "Default")
      (node (ref "J1") (pin "J2_12") (pinfunction "PH11_J2_12") (pintype "passive"))
    )
    (net (code "130") (name "unconnected-(J1-PH12-PadJ2_24)") (class "Default")
      (node (ref "J1") (pin "J2_24") (pinfunction "PH12_J2_24") (pintype "passive"))
    )
    (net (code "131") (name "unconnected-(J1-PH14-PadJ2_29)") (class "Default")
      (node (ref "J1") (pin "J2_29") (pinfunction "PH14_J2_29") (pintype "passive"))
    )
    (net (code "132") (name "unconnected-(J1-PH15-PadJ2_28)") (class "Default")
      (node (ref "J1") (pin "J2_28") (pinfunction "PH15_J2_28") (pintype "passive"))
    )
    (net (code "133") (name "unconnected-(J1-PI7-PadJ2_39)") (class "Default")
      (node (ref "J1") (pin "J2_39") (pinfunction "PI7_J2_39") (pintype "passive"))
    )
    (net (code "134") (name "unconnected-(J1-PI8-PadJ2_40)") (class "Default")
      (node (ref "J1") (pin "J2_40") (pinfunction "PI8_J2_40") (pintype "passive"))
    )
    (net (code "135") (name "unconnected-(J1-RESET-PadJ1_10)") (class "Default")
      (node (ref "J1") (pin "J1_10") (pinfunction "RESET_J1_10") (pintype "passive"))
    )
    (net (code "136") (name "unconnected-(J1-VBAT-PadJ1_29)") (class "Default")
      (node (ref "J1") (pin "J1_29") (pinfunction "VBAT_J1_29") (pintype "passive"))
    )
    (net (code "137") (name "unconnected-(J1-VREF+-PadJ1_2)") (class "Default")
      (node (ref "J1") (pin "J1_2") (pinfunction "VREF+_J1_2") (pintype "passive"))
    )
    (net (code "138") (name "unconnected-(P4-Pad4)") (class "Default")
      (node (ref "P4") (pin "4") (pinfunction "4_4") (pintype "passive+no_connect"))
    )
    (net (code "139") (name "unconnected-(U2-CS-Pad8)") (class "Default")
      (node (ref "U2") (pin "8") (pinfunction "CS_8") (pintype "passive+no_connect"))
    )
    (net (code "140") (name "unconnected-(U2-CTR-Pad3)") (class "Default")
      (node (ref "U2") (pin "3") (pinfunction "CTR_3") (pintype "passive"))
    )
    (net (code "141") (name "unconnected-(U2-NC-Pad5)") (class "Default")
      (node (ref "U2") (pin "5") (pinfunction "NC_5") (pintype "passive+no_connect"))
    )
    (net (code "142") (name "unconnected-(U3-C-Pad10)") (class "Default")
      (node (ref "U3") (pin "10") (pinfunction "C_10") (pintype "passive"))
    )
    (net (code "143") (name "unconnected-(U3-D-Pad14)") (class "Default")
      (node (ref "U3") (pin "14") (pinfunction "D_14") (pintype "passive"))
    )
    (net (code "144") (name "unconnected-(U3-~{C}-Pad11)") (class "Default")
      (node (ref "U3") (pin "11") (pinfunction "~{C}_11") (pintype "passive"))
    )
    (net (code "145") (name "unconnected-(U3-~{D}-Pad13)") (class "Default")
      (node (ref "U3") (pin "13") (pinfunction "~{D}_13") (pintype "passive"))
    )
  )
)
